# drawdio_v1.net
KiCad netlist of a schematic drawn in EAGLE
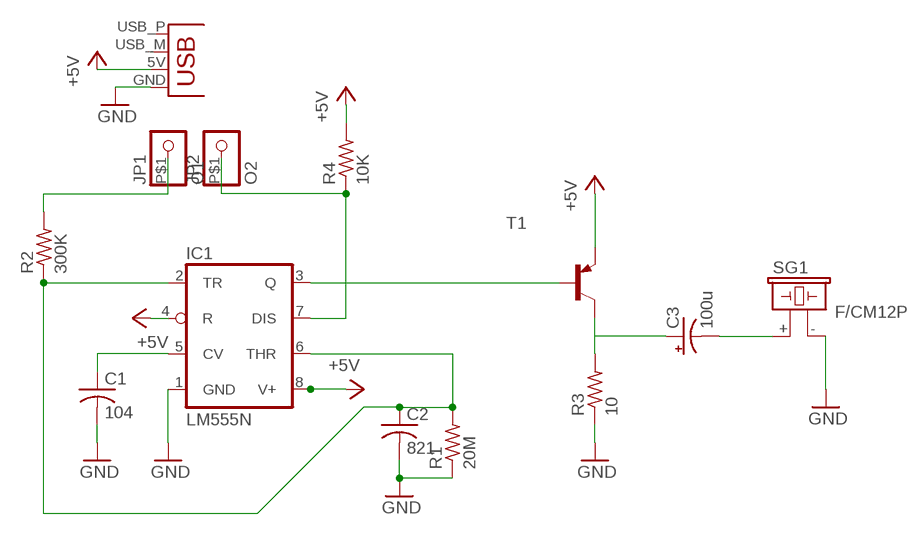
[diagram p0: schematic, sheet 1]

(export (version "E")
  (design (tool "Eeschema 10.0.6"))
  (components
    (comp (ref "C1")
      (value "104")
      (footprint "eagle-import:C025-030X050")
      (libsource (lib "eagle-import") (part "C-US025-030X050"))
    )
    (comp (ref "C2")
      (value "821")
      (footprint "eagle-import:C050-024X044")
      (libsource (lib "eagle-import") (part "C-US050-024X044"))
    )
    (comp (ref "C3")
      (value "100u")
      (footprint "eagle-import:E2,5-6E")
      (libsource (lib "eagle-import") (part "CPOL-USE2,5-6E"))
    )
    (comp (ref "IC1")
      (value "LM555N")
      (footprint "eagle-import:DIL08")
      (libsource (lib "eagle-import") (part "555NLM"))
    )
    (comp (ref "JP1")
      (value "O1")
      (footprint "eagle-import:1X1-BIGPOGO")
      (libsource (lib "eagle-import") (part "PINHD-1X1-BIGPOGO"))
    )
    (comp (ref "JP2")
      (value "O2")
      (footprint "eagle-import:1X1-BIGPOGO")
      (libsource (lib "eagle-import") (part "PINHD-1X1-BIGPOGO"))
    )
    (comp (ref "R1")
      (value "20M")
      (footprint "eagle-import:0207_7")
      (libsource (lib "eagle-import") (part "R-US_0207/7"))
    )
    (comp (ref "R2")
      (value "300K")
      (footprint "eagle-import:0207_7")
      (libsource (lib "eagle-import") (part "R-US_0207/7"))
    )
    (comp (ref "R3")
      (value "10")
      (footprint "eagle-import:0207_7")
      (libsource (lib "eagle-import") (part "R-US_0207/7"))
    )
    (comp (ref "R4")
      (value "10K")
      (footprint "eagle-import:0207_7")
      (libsource (lib "eagle-import") (part "R-US_0207/7"))
    )
    (comp (ref "SG1")
      (value "F/CM12P")
      (footprint "eagle-import:F_CM12P")
      (libsource (lib "eagle-import") (part "F/CM12P"))
    )
    (comp (ref "T1")
      (value "MPS2907A-PNP-TO92-CBE")
      (footprint "eagle-import:TO92-CBE")
      (libsource (lib "eagle-import") (part "-PNP-TO92-CBEMPS2907A"))
    )
    (comp (ref "X1")
      (value "USBPCB")
      (footprint "eagle-import:USB-A-PCB")
      (libsource (lib "eagle-import") (part "USBPCB"))
    )
  )
  (nets
    (net (code "1") (name "+5V") (class "Default")
      (node (ref "IC1") (pin "4") (pinfunction "R_4") (pintype "input"))
      (node (ref "IC1") (pin "8") (pinfunction "V+_8") (pintype "power_in"))
      (node (ref "R4") (pin "2") (pinfunction "2_2") (pintype "passive"))
      (node (ref "T1") (pin "E") (pinfunction "E_E") (pintype "passive"))
      (node (ref "X1") (pin "5V") (pinfunction "VBUS_5V") (pintype "bidirectional"))
    )
    (net (code "2") (name "GND") (class "Default")
      (node (ref "C1") (pin "2") (pinfunction "2_2") (pintype "passive"))
      (node (ref "C2") (pin "2") (pinfunction "2_2") (pintype "passive"))
      (node (ref "IC1") (pin "1") (pinfunction "GND_1") (pintype "power_in"))
      (node (ref "R1") (pin "1") (pinfunction "1_1") (pintype "passive"))
      (node (ref "R3") (pin "1") (pinfunction "1_1") (pintype "passive"))
      (node (ref "SG1") (pin "-") (pinfunction "2_-") (pintype "passive"))
      (node (ref "X1") (pin "GND") (pinfunction "GND_GND") (pintype "bidirectional"))
    )
    (net (code "3") (name "Net-(C3-Pad+)") (class "Default")
      (node (ref "C3") (pin "+") (pinfunction "+_+") (pintype "passive"))
      (node (ref "R3") (pin "2") (pinfunction "2_2") (pintype "passive"))
      (node (ref "T1") (pin "C") (pinfunction "C_C") (pintype "passive"))
    )
    (net (code "4") (name "Net-(IC1-CV)") (class "Default")
      (node (ref "C1") (pin "1") (pinfunction "1_1") (pintype "passive"))
      (node (ref "IC1") (pin "5") (pinfunction "CV_5") (pintype "input"))
    )
    (net (code "5") (name "Net-(IC1-DIS)") (class "Default")
      (node (ref "IC1") (pin "7") (pinfunction "DIS_7") (pintype "input"))
      (node (ref "JP2") (pin "P$1") (pinfunction "1_P$1") (pintype "passive"))
      (node (ref "R4") (pin "1") (pinfunction "1_1") (pintype "passive"))
    )
    (net (code "6") (name "Net-(IC1-Q)") (class "Default")
      (node (ref "IC1") (pin "3") (pinfunction "Q_3") (pintype "output"))
      (node (ref "T1") (pin "B") (pinfunction "B_B") (pintype "passive"))
    )
    (net (code "7") (name "Net-(IC1-THR)") (class "Default")
      (node (ref "C2") (pin "1") (pinfunction "1_1") (pintype "passive"))
      (node (ref "IC1") (pin "2") (pinfunction "TR_2") (pintype "input"))
      (node (ref "IC1") (pin "6") (pinfunction "THR_6") (pintype "input"))
      (node (ref "R1") (pin "2") (pinfunction "2_2") (pintype "passive"))
      (node (ref "R2") (pin "1") (pinfunction "1_1") (pintype "passive"))
    )
    (net (code "8") (name "Net-(JP1-1)") (class "Default")
      (node (ref "JP1") (pin "P$1") (pinfunction "1_P$1") (pintype "passive"))
      (node (ref "R2") (pin "2") (pinfunction "2_2") (pintype "passive"))
    )
    (net (code "9") (name "Net-(SG1-1)") (class "Default")
      (node (ref "C3") (pin "-") (pinfunction "-_-") (pintype "passive"))
      (node (ref "SG1") (pin "+") (pinfunction "1_+") (pintype "passive"))
    )
    (net (code "10") (name "unconnected-(X1-D+-PadUSB_P)") (class "Default")
      (node (ref "X1") (pin "USB_P") (pinfunction "D+_USB_P") (pintype "bidirectional"))
    )
    (net (code "11") (name "unconnected-(X1-D--PadUSB_M)") (class "Default")
      (node (ref "X1") (pin "USB_M") (pinfunction "D-_USB_M") (pintype "bidirectional"))
    )
  )
)
